# Regulator.net
KiCad netlist of a schematic drawn in Altium Designer
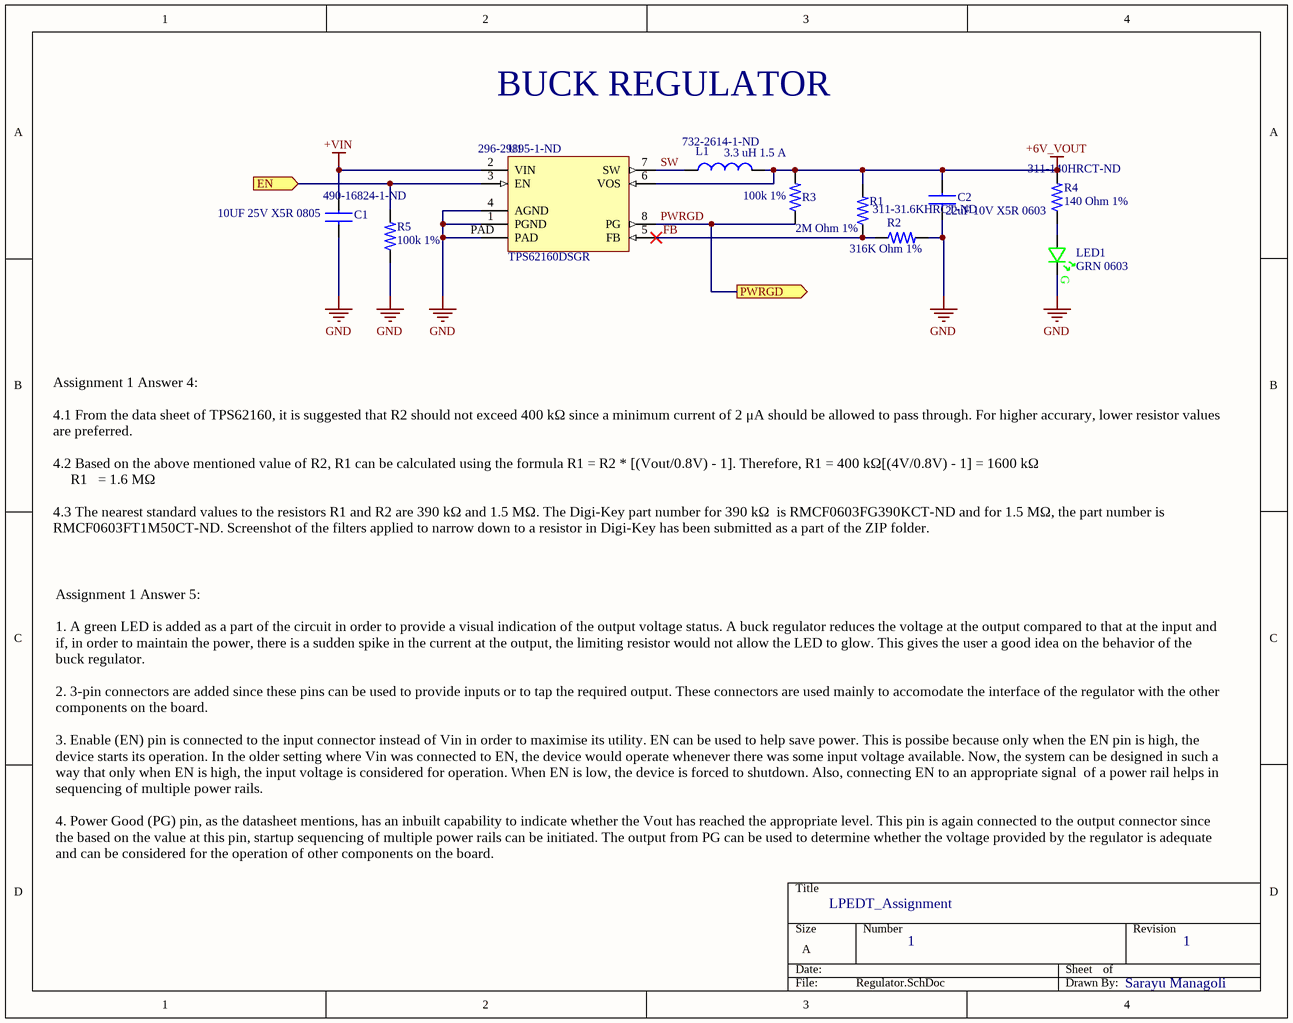
[diagram p0: Regulator.SchDoc]

(export (version "E")
  (design (tool "Eeschema 10.0.6"))
  (components
    (comp (ref "C1")
      (value "10UF 25V X5R 0805")
      (footprint "CAP_2012X14")
      (description "CAP CER 10UF 25V X5R 0805")
      (fields
        (field (name "MANUFACTURER") "Murata")
        (field (name "MANUFACTURER PART NUMBER") "GRM21BR61E106KA73K")
        (field (name "SUPPLIER PART NUMBER 1") "490-16824-1-ND")
      )
      (libsource (lib "LPEDT_Parts") (part "GRM21BR61E106KA73K"))
    )
    (comp (ref "C2")
      (value "22uF 10V X5R 0603")
      (footprint "CAP_0603_1MM")
      (description "CAP CER 22UF 10V X5R 0603")
      (fields
        (field (name "MANUFACTURER") "Murata")
        (field (name "MANUFACTURER PART NUMBER") "GRM188R61A226ME15D")
      )
      (libsource (lib "LPEDT_Parts") (part "GRM188R61A226ME15D"))
    )
    (comp (ref "L1")
      (value "3.3 uH 1.5 A")
      (footprint "IND_2828x30")
      (fields
        (field (name "MANUFACTURER") "Wurth Electronics")
        (field (name "MANUFACTURER PART NUMBER") "744025003")
        (field (name "TOLERANCE") "20%")
        (field (name "SUPPLIER PART NUMBER 1") "732-2614-1-ND")
      )
      (libsource (lib "LPEDT_Parts") (part "744025003"))
    )
    (comp (ref "LED1")
      (value "GRN 0603")
      (footprint "LED_0603_GRN_WL-SMCW")
      (description "LED, 0603, GREEN, 430MCD, 520NM")
      (fields
        (field (name "MANUFACTURER") "Wurth Electronics")
        (field (name "MANUFACTURER PART NUMBER") "150060GS75000")
      )
      (libsource (lib "LPEDT_Parts") (part "150060GS75000"))
    )
    (comp (ref "R1")
      (value "2M Ohm 1%")
      (footprint "RES_0603_1608X06")
      (description "Res Thick Film 0603 2M Ohm 1% 0.1W(1/10W) +/-100ppm/ßC Epoxy SMD T/R")
      (fields
        (field (name "MANUFACTURER") "Yageo")
        (field (name "MANUFACTURER PART NUMBER") "RC0603FR-072ML")
      )
      (libsource (lib "LPEDT_Parts") (part "RC0603FR-072ML"))
    )
    (comp (ref "R2")
      (value "316K Ohm 1%")
      (footprint "RES_0603_1608X06")
      (description "Res Thick Film 0603 31.6K Ohm 1% 0.1W(1/10W) ?100ppm/?C Molded SMD Paper T/R")
      (fields
        (field (name "MANUFACTURER") "Yageo")
        (field (name "MANUFACTURER PART NUMBER") "RC0603FR-0731K6L")
        (field (name "SUPPLIER PART NUMBER 1") "311-31.6KHRCT-ND")
      )
      (libsource (lib "LPEDT_Parts") (part "RC0603FR-0731K6L"))
    )
    (comp (ref "R3")
      (value "100k 1%")
      (footprint "RES_0603_1608X06")
      (description "RES SMD 100K OHM 1% 1/10W 0603")
      (fields
        (field (name "MANUFACTURER") "Yageo")
        (field (name "MANUFACTURER PART NUMBER") "RC0603FR-07100KL")
      )
      (libsource (lib "LPEDT_Parts") (part "RC0603FR-07100KL"))
    )
    (comp (ref "R4")
      (value "140 Ohm 1%")
      (footprint "RES_0603_1608X06")
      (description "Thick Film Resistors 140 OHM 1%")
      (fields
        (field (name "MANUFACTURER") "Yageo")
        (field (name "MANUFACTURER PART NUMBER") "RC0603FR-07140RL")
        (field (name "SUPPLIER PART NUMBER 1") "311-140HRCT-ND")
      )
      (libsource (lib "LPEDT_Parts") (part "RC0603FR-07140RL"))
    )
    (comp (ref "R5")
      (value "100k 1%")
      (footprint "RES_0603_1608X06")
      (description "RES SMD 100K OHM 1% 1/10W 0603")
      (fields
        (field (name "MANUFACTURER") "Yageo")
        (field (name "MANUFACTURER PART NUMBER") "RC0603FR-07100KL")
      )
      (libsource (lib "LPEDT_Parts") (part "RC0603FR-07100KL"))
    )
    (comp (ref "U1")
      (value "TPS62160DSGR")
      (footprint "8-DFN_2x2")
      (description "IC REG BUCK ADJ 1A SYNC 8WSON")
      (fields
        (field (name "MANUFACTURER") "Texas Instruments")
        (field (name "SUPPLIER PART NUMBER 1") "296-29895-1-ND")
      )
      (libsource (lib "LPEDT_Parts") (part "TPS62160DSGR"))
    )
  )
  (nets
    (net (code "1") (name "+6V_VOUT") (class "Default")
      (node (ref "C2") (pin "1") (pinfunction "1_1") (pintype "passive"))
      (node (ref "L1") (pin "2") (pinfunction "2_2") (pintype "passive"))
      (node (ref "R1") (pin "2") (pinfunction "2_2") (pintype "passive"))
      (node (ref "R3") (pin "2") (pinfunction "2_2") (pintype "passive"))
      (node (ref "R4") (pin "2") (pinfunction "2_2") (pintype "passive"))
      (node (ref "U1") (pin "6") (pinfunction "VOS_6") (pintype "input"))
    )
    (net (code "2") (name "+VIN") (class "Default")
      (node (ref "C1") (pin "1") (pinfunction "1_1") (pintype "passive"))
      (node (ref "U1") (pin "2") (pinfunction "VIN_2") (pintype "power_in"))
    )
    (net (code "3") (name "/EN") (class "Default")
      (node (ref "R5") (pin "2") (pinfunction "2_2") (pintype "passive"))
      (node (ref "U1") (pin "3") (pinfunction "EN_3") (pintype "input"))
    )
    (net (code "4") (name "/FB") (class "Default")
      (node (ref "R1") (pin "1") (pinfunction "1_1") (pintype "passive"))
      (node (ref "R2") (pin "1") (pinfunction "1_1") (pintype "passive"))
      (node (ref "U1") (pin "5") (pinfunction "FB_5") (pintype "input"))
    )
    (net (code "5") (name "/PWRGD") (class "Default")
      (node (ref "R3") (pin "1") (pinfunction "1_1") (pintype "passive"))
      (node (ref "U1") (pin "8") (pinfunction "PG_8") (pintype "output"))
    )
    (net (code "6") (name "/SW") (class "Default")
      (node (ref "L1") (pin "1") (pinfunction "1_1") (pintype "passive"))
      (node (ref "U1") (pin "7") (pinfunction "SW_7") (pintype "output"))
    )
    (net (code "7") (name "GND") (class "Default")
      (node (ref "C1") (pin "2") (pinfunction "2_2") (pintype "passive"))
      (node (ref "C2") (pin "2") (pinfunction "2_2") (pintype "passive"))
      (node (ref "LED1") (pin "C") (pinfunction "C_C") (pintype "passive"))
      (node (ref "R2") (pin "2") (pinfunction "2_2") (pintype "passive"))
      (node (ref "R5") (pin "1") (pinfunction "1_1") (pintype "passive"))
      (node (ref "U1") (pin "1") (pinfunction "PGND_1") (pintype "power_in"))
      (node (ref "U1") (pin "4") (pinfunction "AGND_4") (pintype "power_in"))
      (node (ref "U1") (pin "PAD") (pinfunction "PAD_PAD") (pintype "power_in"))
    )
    (net (code "8") (name "Net-(LED1-PadA)") (class "Default")
      (node (ref "LED1") (pin "A") (pinfunction "A_A") (pintype "passive"))
      (node (ref "R4") (pin "1") (pinfunction "1_1") (pintype "passive"))
    )
  )
)
